# SDNL.net
KiCad netlist of a schematic drawn in Altium Designer
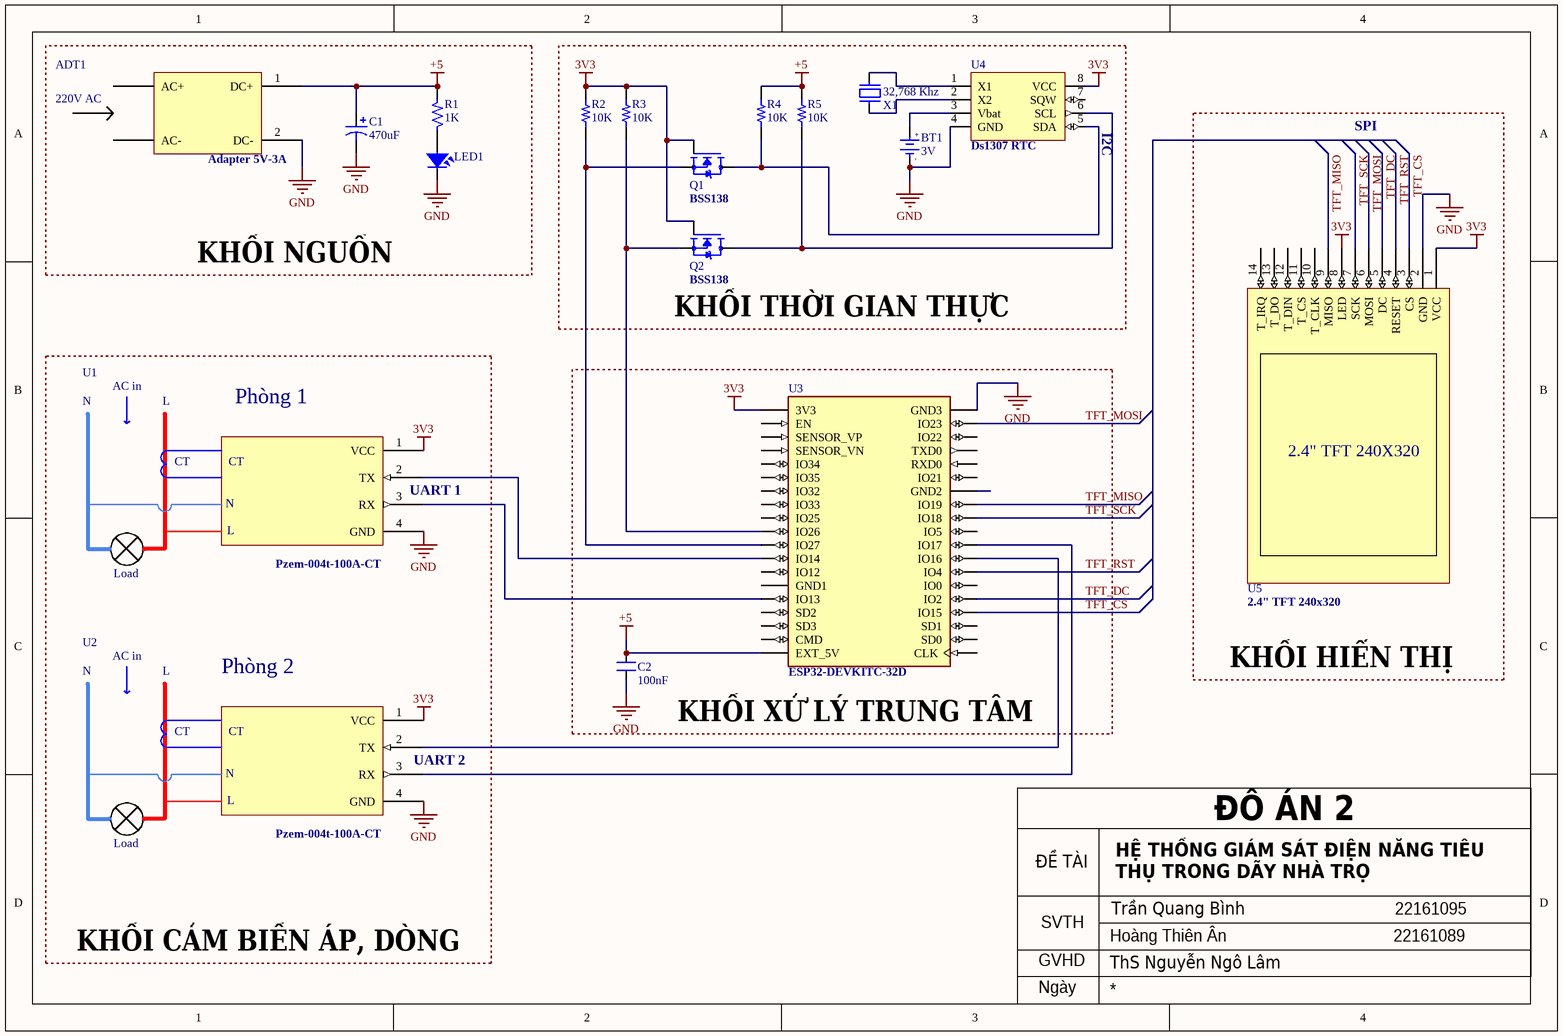
[diagram p0: SDNL.SchDoc]

(export (version "E")
  (design (tool "Eeschema 10.0.6"))
  (components
    (comp (ref "ADT1") (value "Adapter 5V-3A") (libsource (lib "Adapter5V") (part "Adapter 5V")))
    (comp (ref "BT1")
      (value "3V")
      (footprint "PIN3V")
      (description "Battery 3VDC")
      (libsource (lib "syhaunguyen") (part "PIN 3V"))
    )
    (comp (ref "C1")
      (value "470uF")
      (footprint "C8mm")
      (description "Polarized Capacitor (Axial)")
      (fields (field (name "PUBLISHER") "Altium Limited"))
      (libsource (lib "My library altium") (part "Cap Pol"))
    )
    (comp (ref "C2")
      (value "100nF")
      (footprint "CN1")
      (description "Cap np  1pF - 472pF")
      (libsource (lib "syhaunguyen") (part "CN1"))
    )
    (comp (ref "LED1")
      (value "LED")
      (footprint "LED-5TRED")
      (description "LED Single colour Green and Red")
      (libsource (lib "syhaunguyen") (part "LED"))
    )
    (comp (ref "Q1")
      (value "BSS138")
      (footprint "SOT95P240X111-3N")
      (description "N-Channel 50 V 220mA (Ta) 350mW (Ta) Surface Mount SOT-23-3")
      (fields (field (name "MF") "onsemi"))
      (libsource (lib "BSS138") (part "BSS138"))
    )
    (comp (ref "Q2")
      (value "BSS138")
      (footprint "SOT95P240X111-3N")
      (description "N-Channel 50 V 220mA (Ta) 350mW (Ta) Surface Mount SOT-23-3")
      (fields (field (name "MF") "onsemi"))
      (libsource (lib "BSS138") (part "BSS138"))
    )
    (comp (ref "R1")
      (value "1K")
      (footprint "R1/4W")
      (description "Resistor 1/4W")
      (libsource (lib "syhaunguyen") (part "R"))
    )
    (comp (ref "R2")
      (value "10K")
      (description "SMT Resistor")
      (libsource (lib "Altium Database Library V2") (part "Resistor"))
    )
    (comp (ref "R3")
      (value "10K")
      (description "SMT Resistor")
      (libsource (lib "Altium Database Library V2") (part "Resistor"))
    )
    (comp (ref "R4")
      (value "10K")
      (description "SMT Resistor")
      (libsource (lib "Altium Database Library V2") (part "Resistor"))
    )
    (comp (ref "R5")
      (value "10K")
      (description "SMT Resistor")
      (libsource (lib "Altium Database Library V2") (part "Resistor"))
    )
    (comp (ref "U1")
      (value "Pzem-004t-100A-CT")
      (footprint "Pzem-004t - duplicate1")
      (libsource (lib "Pzem-004t") (part "Pzem-004t-100A-CT"))
    )
    (comp (ref "U2")
      (value "Pzem-004t-100A-CT")
      (footprint "Pzem-004t - duplicate1")
      (libsource (lib "Pzem-004t") (part "Pzem-004t-100A-CT"))
    )
    (comp (ref "U3")
      (value "ESP32-DEVKITC-32D")
      (footprint "MODULE_ESP32-DEVKITC-32D")
      (description "WiFi Development Tools (802.11) ESP32 General Development Kit, ESP32-WROOM-32D on the board")
      (fields (field (name "MF") "Espressif Systems"))
      (libsource (lib "ESP32-DEVKITC-32D") (part "ESP32-DEVKITC-32D"))
    )
    (comp (ref "U4") (value "Ds1307 RTC") (footprint "Ds1307") (libsource (lib "Ds1307") (part "Ds1307")))
    (comp (ref "U5")
      (value "2.4\" TFT 240x320")
      (footprint "TFT")
      (libsource (lib "TFT 2.4 inches SPI") (part "2.4{dblquote} TFT 240x320"))
    )
    (comp (ref "X1")
      (value "32,768 Khz")
      (footprint "XT32k")
      (description "Crystal 32,768kHz for timer real")
      (libsource (lib "syhaunguyen") (part "XT32k"))
    )
  )
  (nets
    (net (code "1") (name "+5") (class "Default")
      (node (ref "ADT1") (pin "1") (pinfunction "DC+_1") (pintype "power_in"))
      (node (ref "C1") (pin "1") (pinfunction "1_1") (pintype "passive"))
      (node (ref "C2") (pin "2") (pinfunction "2_2") (pintype "passive"))
      (node (ref "R1") (pin "2") (pinfunction "2_2") (pintype "passive"))
      (node (ref "R4") (pin "2") (pinfunction "2_2") (pintype "passive"))
      (node (ref "R5") (pin "2") (pinfunction "2_2") (pintype "passive"))
      (node (ref "U3") (pin "19") (pinfunction "EXT_5V_19") (pintype "power_in"))
    )
    (net (code "3") (name "/TFT_CS") (class "Default")
      (node (ref "U3") (pin "35") (pinfunction "IO15_35") (pintype "bidirectional"))
      (node (ref "U5") (pin "3") (pinfunction "CS_3") (pintype "bidirectional"))
    )
    (net (code "4") (name "/TFT_DC") (class "Default")
      (node (ref "U3") (pin "34") (pinfunction "IO2_34") (pintype "bidirectional"))
      (node (ref "U5") (pin "5") (pinfunction "DC_5") (pintype "bidirectional"))
    )
    (net (code "5") (name "/TFT_MISO") (class "Default")
      (node (ref "U3") (pin "27") (pinfunction "IO19_27") (pintype "bidirectional"))
      (node (ref "U5") (pin "9") (pinfunction "MISO_9") (pintype "bidirectional"))
    )
    (net (code "6") (name "/TFT_MOSI") (class "Default")
      (node (ref "U3") (pin "21") (pinfunction "IO23_21") (pintype "bidirectional"))
      (node (ref "U5") (pin "6") (pinfunction "MOSI_6") (pintype "bidirectional"))
    )
    (net (code "7") (name "/TFT_RST") (class "Default")
      (node (ref "U3") (pin "32") (pinfunction "IO4_32") (pintype "bidirectional"))
      (node (ref "U5") (pin "4") (pinfunction "RESET_4") (pintype "bidirectional"))
    )
    (net (code "8") (name "/TFT_SCK") (class "Default")
      (node (ref "U3") (pin "28") (pinfunction "IO18_28") (pintype "bidirectional"))
      (node (ref "U5") (pin "7") (pinfunction "SCK_7") (pintype "bidirectional"))
    )
    (net (code "9") (name "3V3") (class "Default")
      (node (ref "Q1") (pin "1") (pinfunction "G_1") (pintype "passive"))
      (node (ref "Q2") (pin "1") (pinfunction "G_1") (pintype "passive"))
      (node (ref "R2") (pin "2") (pinfunction "2_2") (pintype "passive"))
      (node (ref "R3") (pin "2") (pinfunction "2_2") (pintype "passive"))
      (node (ref "U1") (pin "1") (pinfunction "VCC_1") (pintype "passive"))
      (node (ref "U2") (pin "1") (pinfunction "VCC_1") (pintype "passive"))
      (node (ref "U3") (pin "1") (pinfunction "3V3_1") (pintype "power_in"))
      (node (ref "U4") (pin "8") (pinfunction "VCC_8") (pintype "power_in"))
      (node (ref "U5") (pin "1") (pinfunction "VCC_1") (pintype "power_in"))
      (node (ref "U5") (pin "8") (pinfunction "LED_8") (pintype "bidirectional"))
    )
    (net (code "10") (name "GND") (class "Default")
      (node (ref "ADT1") (pin "2") (pinfunction "DC-_2") (pintype "passive"))
      (node (ref "BT1") (pin "2") (pinfunction "GND_2") (pintype "passive"))
      (node (ref "C1") (pin "2") (pinfunction "2_2") (pintype "passive"))
      (node (ref "C2") (pin "1") (pinfunction "1_1") (pintype "passive"))
      (node (ref "LED1") (pin "2") (pinfunction "2_2") (pintype "passive"))
      (node (ref "U1") (pin "4") (pinfunction "GND_4") (pintype "passive"))
      (node (ref "U2") (pin "4") (pinfunction "GND_4") (pintype "passive"))
      (node (ref "U3") (pin "20") (pinfunction "GND3_20") (pintype "power_in"))
      (node (ref "U4") (pin "4") (pinfunction "GND_4") (pintype "power_in"))
      (node (ref "U5") (pin "2") (pinfunction "GND_2") (pintype "power_in"))
    )
    (net (code "11") (name "Net-(BT1-+3V)") (class "Default")
      (node (ref "BT1") (pin "1") (pinfunction "+3V_1") (pintype "passive"))
      (node (ref "U4") (pin "3") (pinfunction "Vbat_3") (pintype "power_in"))
    )
    (net (code "12") (name "Net-(LED1-Pad1)") (class "Default")
      (node (ref "LED1") (pin "1") (pinfunction "1_1") (pintype "passive"))
      (node (ref "R1") (pin "1") (pinfunction "1_1") (pintype "passive"))
    )
    (net (code "13") (name "Net-(Q1-D)") (class "Default")
      (node (ref "Q1") (pin "3") (pinfunction "D_3") (pintype "passive"))
      (node (ref "R4") (pin "1") (pinfunction "1_1") (pintype "passive"))
      (node (ref "U4") (pin "5") (pinfunction "SDA_5") (pintype "bidirectional"))
    )
    (net (code "14") (name "Net-(Q1-S)") (class "Default")
      (node (ref "Q1") (pin "2") (pinfunction "S_2") (pintype "passive"))
      (node (ref "R2") (pin "1") (pinfunction "1_1") (pintype "passive"))
      (node (ref "U3") (pin "11") (pinfunction "IO27_11") (pintype "bidirectional"))
    )
    (net (code "15") (name "Net-(Q2-D)") (class "Default")
      (node (ref "Q2") (pin "3") (pinfunction "D_3") (pintype "passive"))
      (node (ref "R5") (pin "1") (pinfunction "1_1") (pintype "passive"))
      (node (ref "U4") (pin "6") (pinfunction "SCL_6") (pintype "output"))
    )
    (net (code "16") (name "Net-(Q2-S)") (class "Default")
      (node (ref "Q2") (pin "2") (pinfunction "S_2") (pintype "passive"))
      (node (ref "R3") (pin "1") (pinfunction "1_1") (pintype "passive"))
      (node (ref "U3") (pin "10") (pinfunction "IO26_10") (pintype "bidirectional"))
    )
    (net (code "17") (name "Net-(U1-RX)") (class "Default")
      (node (ref "U1") (pin "3") (pinfunction "RX_3") (pintype "output"))
      (node (ref "U3") (pin "15") (pinfunction "IO13_15") (pintype "bidirectional"))
    )
    (net (code "18") (name "Net-(U1-TX)") (class "Default")
      (node (ref "U1") (pin "2") (pinfunction "TX_2") (pintype "input"))
      (node (ref "U3") (pin "12") (pinfunction "IO14_12") (pintype "bidirectional"))
    )
    (net (code "19") (name "Net-(U2-RX)") (class "Default")
      (node (ref "U2") (pin "3") (pinfunction "RX_3") (pintype "output"))
      (node (ref "U3") (pin "30") (pinfunction "IO17_30") (pintype "bidirectional"))
    )
    (net (code "20") (name "Net-(U2-TX)") (class "Default")
      (node (ref "U2") (pin "2") (pinfunction "TX_2") (pintype "input"))
      (node (ref "U3") (pin "31") (pinfunction "IO16_31") (pintype "bidirectional"))
    )
    (net (code "21") (name "Net-(U4-X1)") (class "Default")
      (node (ref "U4") (pin "1") (pinfunction "X1_1") (pintype "power_in"))
      (node (ref "X1") (pin "2") (pinfunction "2_2") (pintype "passive"))
    )
    (net (code "22") (name "Net-(U4-X2)") (class "Default")
      (node (ref "U4") (pin "2") (pinfunction "X2_2") (pintype "power_in"))
      (node (ref "X1") (pin "1") (pinfunction "1_1") (pintype "passive"))
    )
    (net (code "23") (name "unconnected-(ADT1-AC+-Pad)") (class "Default")
      (node (ref "ADT1") (pin "") (pinfunction "AC+_") (pintype "passive"))
    )
    (net (code "24") (name "unconnected-(ADT1-AC--Pad)") (class "Default")
      (node (ref "ADT1") (pin "") (pinfunction "AC-_") (pintype "passive"))
    )
    (net (code "25") (name "unconnected-(U3-CLK-Pad38)") (class "Default")
      (node (ref "U3") (pin "38") (pinfunction "CLK_38") (pintype "input"))
    )
    (net (code "26") (name "unconnected-(U3-CMD-Pad18)") (class "Default")
      (node (ref "U3") (pin "18") (pinfunction "CMD_18") (pintype "bidirectional"))
    )
    (net (code "27") (name "unconnected-(U3-EN-Pad2)") (class "Default")
      (node (ref "U3") (pin "2") (pinfunction "EN_2") (pintype "input"))
    )
    (net (code "28") (name "unconnected-(U3-GND1-Pad14)") (class "Default")
      (node (ref "U3") (pin "14") (pinfunction "GND1_14") (pintype "power_in"))
    )
    (net (code "29") (name "unconnected-(U3-GND2-Pad26)") (class "Default")
      (node (ref "U3") (pin "26") (pinfunction "GND2_26") (pintype "power_in"))
    )
    (net (code "30") (name "unconnected-(U3-IO0-Pad33)") (class "Default")
      (node (ref "U3") (pin "33") (pinfunction "IO0_33") (pintype "bidirectional"))
    )
    (net (code "31") (name "unconnected-(U3-IO5-Pad29)") (class "Default")
      (node (ref "U3") (pin "29") (pinfunction "IO5_29") (pintype "bidirectional"))
    )
    (net (code "32") (name "unconnected-(U3-IO12-Pad13)") (class "Default")
      (node (ref "U3") (pin "13") (pinfunction "IO12_13") (pintype "bidirectional"))
    )
    (net (code "33") (name "unconnected-(U3-IO21-Pad25)") (class "Default")
      (node (ref "U3") (pin "25") (pinfunction "IO21_25") (pintype "bidirectional"))
    )
    (net (code "34") (name "unconnected-(U3-IO22-Pad22)") (class "Default")
      (node (ref "U3") (pin "22") (pinfunction "IO22_22") (pintype "bidirectional"))
    )
    (net (code "35") (name "unconnected-(U3-IO25-Pad9)") (class "Default")
      (node (ref "U3") (pin "9") (pinfunction "IO25_9") (pintype "bidirectional"))
    )
    (net (code "36") (name "unconnected-(U3-IO32-Pad7)") (class "Default")
      (node (ref "U3") (pin "7") (pinfunction "IO32_7") (pintype "bidirectional"))
    )
    (net (code "37") (name "unconnected-(U3-IO33-Pad8)") (class "Default")
      (node (ref "U3") (pin "8") (pinfunction "IO33_8") (pintype "bidirectional"))
    )
    (net (code "38") (name "unconnected-(U3-IO34-Pad5)") (class "Default")
      (node (ref "U3") (pin "5") (pinfunction "IO34_5") (pintype "bidirectional"))
    )
    (net (code "39") (name "unconnected-(U3-IO35-Pad6)") (class "Default")
      (node (ref "U3") (pin "6") (pinfunction "IO35_6") (pintype "bidirectional"))
    )
    (net (code "40") (name "unconnected-(U3-RXD0-Pad24)") (class "Default")
      (node (ref "U3") (pin "24") (pinfunction "RXD0_24") (pintype "input"))
    )
    (net (code "41") (name "unconnected-(U3-SD0-Pad37)") (class "Default")
      (node (ref "U3") (pin "37") (pinfunction "SD0_37") (pintype "bidirectional"))
    )
    (net (code "42") (name "unconnected-(U3-SD1-Pad36)") (class "Default")
      (node (ref "U3") (pin "36") (pinfunction "SD1_36") (pintype "bidirectional"))
    )
    (net (code "43") (name "unconnected-(U3-SD2-Pad16)") (class "Default")
      (node (ref "U3") (pin "16") (pinfunction "SD2_16") (pintype "bidirectional"))
    )
    (net (code "44") (name "unconnected-(U3-SD3-Pad17)") (class "Default")
      (node (ref "U3") (pin "17") (pinfunction "SD3_17") (pintype "bidirectional"))
    )
    (net (code "45") (name "unconnected-(U3-SENSOR_VN-Pad4)") (class "Default")
      (node (ref "U3") (pin "4") (pinfunction "SENSOR_VN_4") (pintype "input"))
    )
    (net (code "46") (name "unconnected-(U3-SENSOR_VP-Pad3)") (class "Default")
      (node (ref "U3") (pin "3") (pinfunction "SENSOR_VP_3") (pintype "input"))
    )
    (net (code "47") (name "unconnected-(U3-TXD0-Pad23)") (class "Default")
      (node (ref "U3") (pin "23") (pinfunction "TXD0_23") (pintype "output"))
    )
    (net (code "48") (name "unconnected-(U4-SQW-Pad7)") (class "Default")
      (node (ref "U4") (pin "7") (pinfunction "SQW_7") (pintype "bidirectional"))
    )
    (net (code "49") (name "unconnected-(U5-T_CLK-Pad10)") (class "Default")
      (node (ref "U5") (pin "10") (pinfunction "T_CLK_10") (pintype "bidirectional"))
    )
    (net (code "50") (name "unconnected-(U5-T_CS-Pad11)") (class "Default")
      (node (ref "U5") (pin "11") (pinfunction "T_CS_11") (pintype "bidirectional"))
    )
    (net (code "51") (name "unconnected-(U5-T_DIN-Pad12)") (class "Default")
      (node (ref "U5") (pin "12") (pinfunction "T_DIN_12") (pintype "bidirectional"))
    )
    (net (code "52") (name "unconnected-(U5-T_DO-Pad13)") (class "Default")
      (node (ref "U5") (pin "13") (pinfunction "T_DO_13") (pintype "bidirectional"))
    )
    (net (code "53") (name "unconnected-(U5-T_IRQ-Pad14)") (class "Default")
      (node (ref "U5") (pin "14") (pinfunction "T_IRQ_14") (pintype "bidirectional"))
    )
  )
)
